# Mainboard.net
KiCad netlist of a schematic drawn in Altium Designer
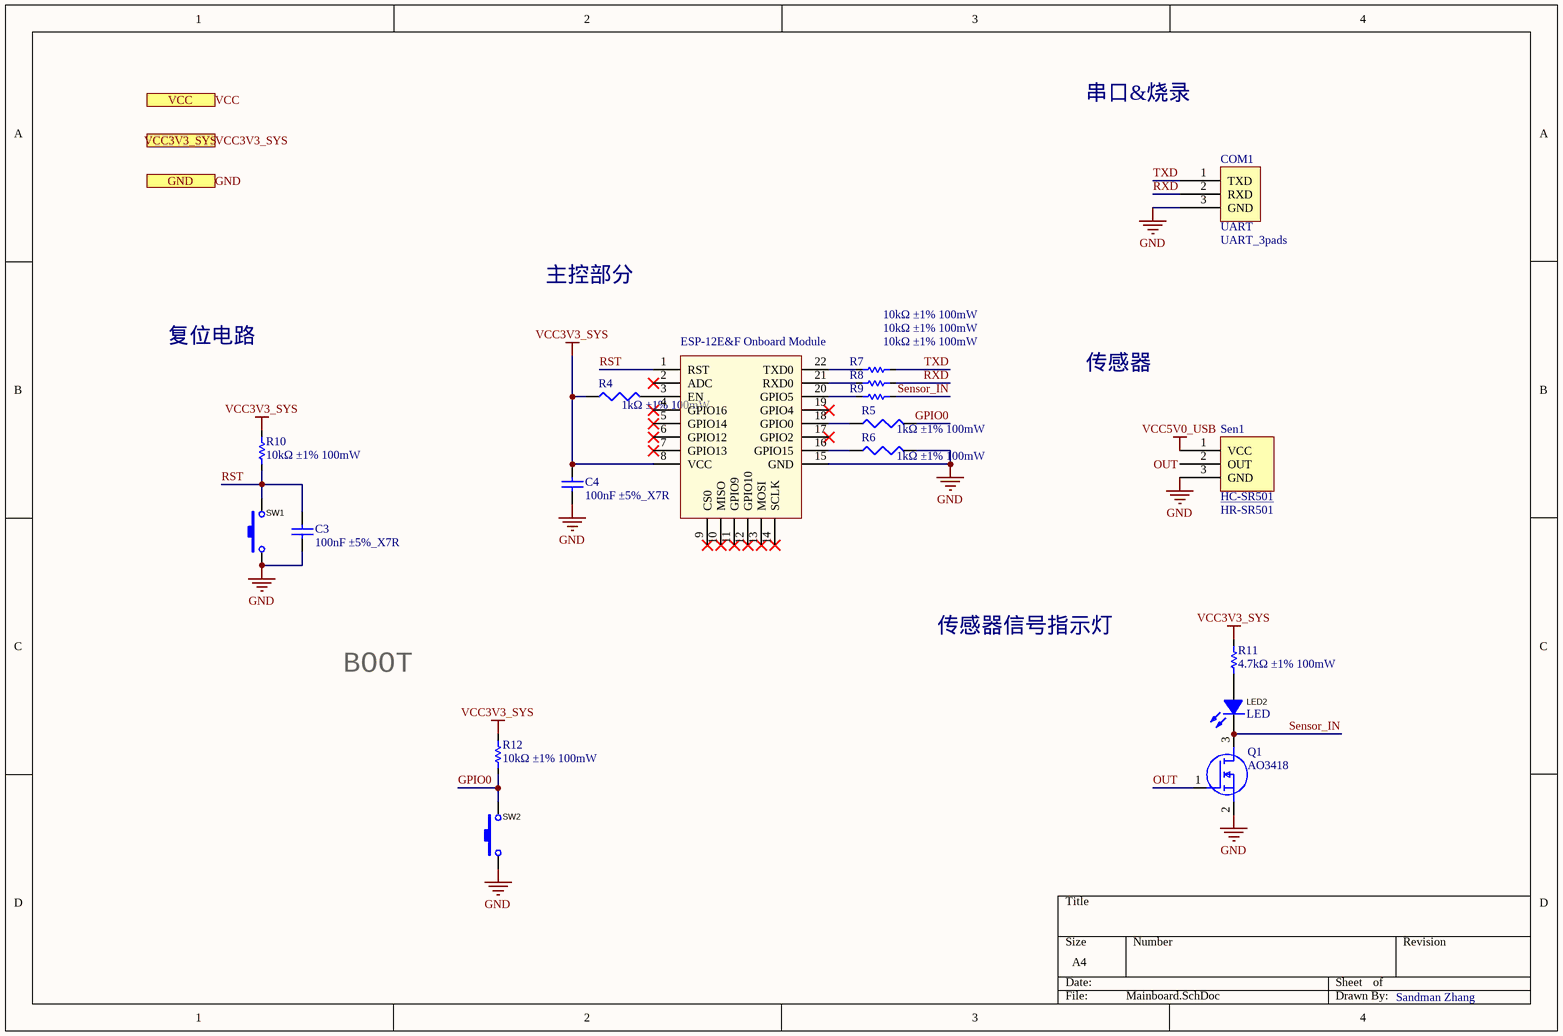
[diagram p0: Mainboard.SchDoc]

(export (version "E")
  (design (tool "Eeschema 10.0.6"))
  (components
    (comp (ref "C3")
      (value "100nF ±5%_X7R")
      (footprint "C0603")
      (description "Capacitor")
      (fields (field (name "PUBLISHER") "Altium Limited"))
      (libsource (lib "Component_Footprints") (part "Cap"))
    )
    (comp (ref "C4")
      (value "100nF ±5%_X7R")
      (footprint "C0603")
      (description "Capacitor")
      (fields (field (name "PUBLISHER") "Altium Limited"))
      (libsource (lib "Component_Footprints") (part "Cap"))
    )
    (comp (ref "COM1")
      (value "UART_3pads")
      (footprint "3pads")
      (libsource (lib "Connectivity_pads") (part "UART_3pads"))
    )
    (comp (ref "LED2")
      (value "LED")
      (footprint "LED0603-RD")
      (fields
        (field (name "MANUFACTURER") "EVERLIGHT(亿光)")
        (field (name "MANUFACTURER PART") "17-21SURC/S530-A2/TR8")
      )
      (libsource (lib "Component") (part "LED"))
    )
    (comp (ref "Q1")
      (value "AO3418")
      (footprint "SamacSys:SOT95P280X125-3N")
      (description "MOSFET (N-Channel)")
      (libsource (lib "*") (part "AO3418"))
    )
    (comp (ref "R4")
      (value "1kΩ ±1% 100mW")
      (footprint "r0402")
      (description "Resistor")
      (fields (field (name "Comment") "Res3") (field (name "PUBLISHER") "Altium Limited"))
      (libsource (lib "Miscellaneous Devices") (part "Res3"))
    )
    (comp (ref "R5")
      (value "1kΩ ±1% 100mW")
      (footprint "r0402")
      (description "Resistor")
      (fields (field (name "Comment") "Res3") (field (name "PUBLISHER") "Altium Limited"))
      (libsource (lib "Miscellaneous Devices") (part "Res3"))
    )
    (comp (ref "R6")
      (value "1kΩ ±1% 100mW")
      (footprint "r0402")
      (description "Resistor")
      (fields (field (name "Comment") "Res3") (field (name "PUBLISHER") "Altium Limited"))
      (libsource (lib "Miscellaneous Devices") (part "Res3"))
    )
    (comp (ref "R7")
      (value "10kΩ ±1% 100mW")
      (footprint "R0402")
      (description "Resistor")
      (fields (field (name "PUBLISHER") "Altium Limited"))
      (libsource (lib "Component_Footprints") (part "Res"))
    )
    (comp (ref "R8")
      (value "10kΩ ±1% 100mW")
      (footprint "R0402")
      (description "Resistor")
      (fields (field (name "PUBLISHER") "Altium Limited"))
      (libsource (lib "Component_Footprints") (part "Res"))
    )
    (comp (ref "R9")
      (value "10kΩ ±1% 100mW")
      (footprint "R0402")
      (description "Resistor")
      (fields (field (name "PUBLISHER") "Altium Limited"))
      (libsource (lib "Component_Footprints") (part "Res"))
    )
    (comp (ref "R10")
      (value "10kΩ ±1% 100mW")
      (footprint "R0402")
      (description "Resistor")
      (fields (field (name "PUBLISHER") "Altium Limited"))
      (libsource (lib "Component_Footprints") (part "Res"))
    )
    (comp (ref "R11")
      (value "4.7kΩ ±1% 100mW")
      (footprint "R0603")
      (description "Resistor")
      (fields (field (name "PUBLISHER") "Altium Limited"))
      (libsource (lib "Component_Footprints") (part "Res"))
    )
    (comp (ref "R12")
      (value "10kΩ ±1% 100mW")
      (footprint "R0402")
      (description "Resistor")
      (fields (field (name "PUBLISHER") "Altium Limited"))
      (libsource (lib "Component_Footprints") (part "Res"))
    )
    (comp (ref "Sen1")
      (value "HR-SR501")
      (footprint "HR-SR501")
      (description "人体红外感应模块")
      (libsource (lib "Common_Modules") (part "HR-SR501"))
    )
    (comp (ref "SW1")
      (value "TS-1185-B-A-B-A")
      (footprint "SW-SMD_L4.0-W3.0-LS5.0")
      (description "触点电流：50mA 额定电压(DC)：12V 电路结构：单刀单掷 安装方式：立贴 带灯：无 作用力：160gf 机械寿命：10万次 带支架：否 轻触开关3x4x2贴片2脚小龟 160gf")
      (fields (field (name "MANUFACTURER") "XKB Connectivity(中国星坤)"))
      (libsource (lib "Component_Footprints") (part "Button"))
    )
    (comp (ref "SW2")
      (value "TS-1185-B-A-B-A")
      (footprint "SW-SMD_L4.0-W3.0-LS5.0")
      (description "触点电流：50mA 额定电压(DC)：12V 电路结构：单刀单掷 安装方式：立贴 带灯：无 作用力：160gf 机械寿命：10万次 带支架：否 轻触开关3x4x2贴片2脚小龟 160gf")
      (fields (field (name "MANUFACTURER") "XKB Connectivity(中国星坤)"))
      (libsource (lib "Component_Footprints") (part "Button"))
    )
    (comp (ref "U2")
      (value "ESP-12E&F Onboard Module")
      (footprint "ESP-12E&F Module")
      (libsource (lib "ESP-12E&F Onboard Module") (part "ESP-12E&F Onboard Module"))
    )
  )
  (nets
    (net (code "1") (name "/GPIO0") (class "Default")
      (node (ref "R12") (pin "1") (pinfunction "1_1") (pintype "passive"))
      (node (ref "R5") (pin "2") (pinfunction "2_2") (pintype "passive"))
      (node (ref "SW2") (pin "2") (pinfunction "2_2") (pintype "passive"))
    )
    (net (code "2") (name "/OUT") (class "Default")
      (node (ref "Q1") (pin "1") (pinfunction "G_1") (pintype "passive"))
      (node (ref "Sen1") (pin "2") (pinfunction "OUT_2") (pintype "passive"))
    )
    (net (code "3") (name "/RST") (class "Default")
      (node (ref "C3") (pin "2") (pinfunction "2_2") (pintype "passive"))
      (node (ref "R10") (pin "1") (pinfunction "1_1") (pintype "passive"))
      (node (ref "SW1") (pin "2") (pinfunction "2_2") (pintype "passive"))
      (node (ref "U2") (pin "1") (pinfunction "RST_1") (pintype "passive"))
    )
    (net (code "4") (name "/RXD") (class "Default")
      (node (ref "COM1") (pin "2") (pinfunction "RXD_2") (pintype "passive"))
      (node (ref "R8") (pin "1") (pinfunction "1_1") (pintype "passive"))
    )
    (net (code "5") (name "/Sensor_IN") (class "Default")
      (node (ref "LED2") (pin "2") (pinfunction "K_2") (pintype "passive"))
      (node (ref "Q1") (pin "3") (pinfunction "D_3") (pintype "passive"))
      (node (ref "R9") (pin "1") (pinfunction "1_1") (pintype "passive"))
    )
    (net (code "6") (name "/TXD") (class "Default")
      (node (ref "COM1") (pin "1") (pinfunction "TXD_1") (pintype "passive"))
      (node (ref "R7") (pin "1") (pinfunction "1_1") (pintype "passive"))
    )
    (net (code "8") (name "GND") (class "Default")
      (node (ref "C3") (pin "1") (pinfunction "1_1") (pintype "passive"))
      (node (ref "C4") (pin "1") (pinfunction "1_1") (pintype "passive"))
      (node (ref "COM1") (pin "3") (pinfunction "GND_3") (pintype "passive"))
      (node (ref "Q1") (pin "2") (pinfunction "S_2") (pintype "passive"))
      (node (ref "R6") (pin "2") (pinfunction "2_2") (pintype "passive"))
      (node (ref "SW1") (pin "1") (pinfunction "1_1") (pintype "passive"))
      (node (ref "SW2") (pin "1") (pinfunction "1_1") (pintype "passive"))
      (node (ref "Sen1") (pin "3") (pinfunction "GND_3") (pintype "passive"))
      (node (ref "U2") (pin "15") (pinfunction "GND_15") (pintype "passive"))
    )
    (net (code "9") (name "Net-(LED2-A)") (class "Default")
      (node (ref "LED2") (pin "1") (pinfunction "A_1") (pintype "passive"))
      (node (ref "R11") (pin "2") (pinfunction "2_2") (pintype "passive"))
    )
    (net (code "10") (name "Net-(U2-EN)") (class "Default")
      (node (ref "R4") (pin "2") (pinfunction "2_2") (pintype "passive"))
      (node (ref "U2") (pin "3") (pinfunction "EN_3") (pintype "passive"))
    )
    (net (code "11") (name "Net-(U2-GPIO0)") (class "Default")
      (node (ref "R5") (pin "1") (pinfunction "1_1") (pintype "passive"))
      (node (ref "U2") (pin "18") (pinfunction "GPIO0_18") (pintype "passive"))
    )
    (net (code "12") (name "Net-(U2-GPIO5)") (class "Default")
      (node (ref "R9") (pin "2") (pinfunction "2_2") (pintype "passive"))
      (node (ref "U2") (pin "20") (pinfunction "GPIO5_20") (pintype "passive"))
    )
    (net (code "13") (name "Net-(U2-GPIO15)") (class "Default")
      (node (ref "R6") (pin "1") (pinfunction "1_1") (pintype "passive"))
      (node (ref "U2") (pin "16") (pinfunction "GPIO15_16") (pintype "passive"))
    )
    (net (code "14") (name "Net-(U2-RXD0)") (class "Default")
      (node (ref "R8") (pin "2") (pinfunction "2_2") (pintype "passive"))
      (node (ref "U2") (pin "21") (pinfunction "RXD0_21") (pintype "passive"))
    )
    (net (code "15") (name "Net-(U2-TXD0)") (class "Default")
      (node (ref "R7") (pin "2") (pinfunction "2_2") (pintype "passive"))
      (node (ref "U2") (pin "22") (pinfunction "TXD0_22") (pintype "passive"))
    )
    (net (code "16") (name "VCC3V3_SYS") (class "Default")
      (node (ref "C4") (pin "2") (pinfunction "2_2") (pintype "passive"))
      (node (ref "R10") (pin "2") (pinfunction "2_2") (pintype "passive"))
      (node (ref "R11") (pin "1") (pinfunction "1_1") (pintype "passive"))
      (node (ref "R12") (pin "2") (pinfunction "2_2") (pintype "passive"))
      (node (ref "R4") (pin "1") (pinfunction "1_1") (pintype "passive"))
      (node (ref "U2") (pin "8") (pinfunction "VCC_8") (pintype "passive"))
    )
    (net (code "17") (name "VCC5V0_USB") (class "Default")
      (node (ref "Sen1") (pin "1") (pinfunction "VCC_1") (pintype "passive"))
    )
    (net (code "18") (name "unconnected-(U2-ADC-Pad2)") (class "Default")
      (node (ref "U2") (pin "2") (pinfunction "ADC_2") (pintype "passive+no_connect"))
    )
    (net (code "19") (name "unconnected-(U2-CS0-Pad9)") (class "Default")
      (node (ref "U2") (pin "9") (pinfunction "CS0_9") (pintype "passive+no_connect"))
    )
    (net (code "20") (name "unconnected-(U2-GPIO2-Pad17)") (class "Default")
      (node (ref "U2") (pin "17") (pinfunction "GPIO2_17") (pintype "passive+no_connect"))
    )
    (net (code "21") (name "unconnected-(U2-GPIO4-Pad19)") (class "Default")
      (node (ref "U2") (pin "19") (pinfunction "GPIO4_19") (pintype "passive+no_connect"))
    )
    (net (code "22") (name "unconnected-(U2-GPIO9-Pad11)") (class "Default")
      (node (ref "U2") (pin "11") (pinfunction "GPIO9_11") (pintype "passive+no_connect"))
    )
    (net (code "23") (name "unconnected-(U2-GPIO10-Pad12)") (class "Default")
      (node (ref "U2") (pin "12") (pinfunction "GPIO10_12") (pintype "passive+no_connect"))
    )
    (net (code "24") (name "unconnected-(U2-GPIO12-Pad6)") (class "Default")
      (node (ref "U2") (pin "6") (pinfunction "GPIO12_6") (pintype "passive+no_connect"))
    )
    (net (code "25") (name "unconnected-(U2-GPIO13-Pad7)") (class "Default")
      (node (ref "U2") (pin "7") (pinfunction "GPIO13_7") (pintype "passive+no_connect"))
    )
    (net (code "26") (name "unconnected-(U2-GPIO14-Pad5)") (class "Default")
      (node (ref "U2") (pin "5") (pinfunction "GPIO14_5") (pintype "passive+no_connect"))
    )
    (net (code "27") (name "unconnected-(U2-GPIO16-Pad4)") (class "Default")
      (node (ref "U2") (pin "4") (pinfunction "GPIO16_4") (pintype "passive+no_connect"))
    )
    (net (code "28") (name "unconnected-(U2-MISO-Pad10)") (class "Default")
      (node (ref "U2") (pin "10") (pinfunction "MISO_10") (pintype "passive+no_connect"))
    )
    (net (code "29") (name "unconnected-(U2-MOSI-Pad13)") (class "Default")
      (node (ref "U2") (pin "13") (pinfunction "MOSI_13") (pintype "passive+no_connect"))
    )
    (net (code "30") (name "unconnected-(U2-SCLK-Pad14)") (class "Default")
      (node (ref "U2") (pin "14") (pinfunction "SCLK_14") (pintype "passive+no_connect"))
    )
  )
)
